# TeknoAmiga.net
KiCad netlist of a schematic drawn in EAGLE
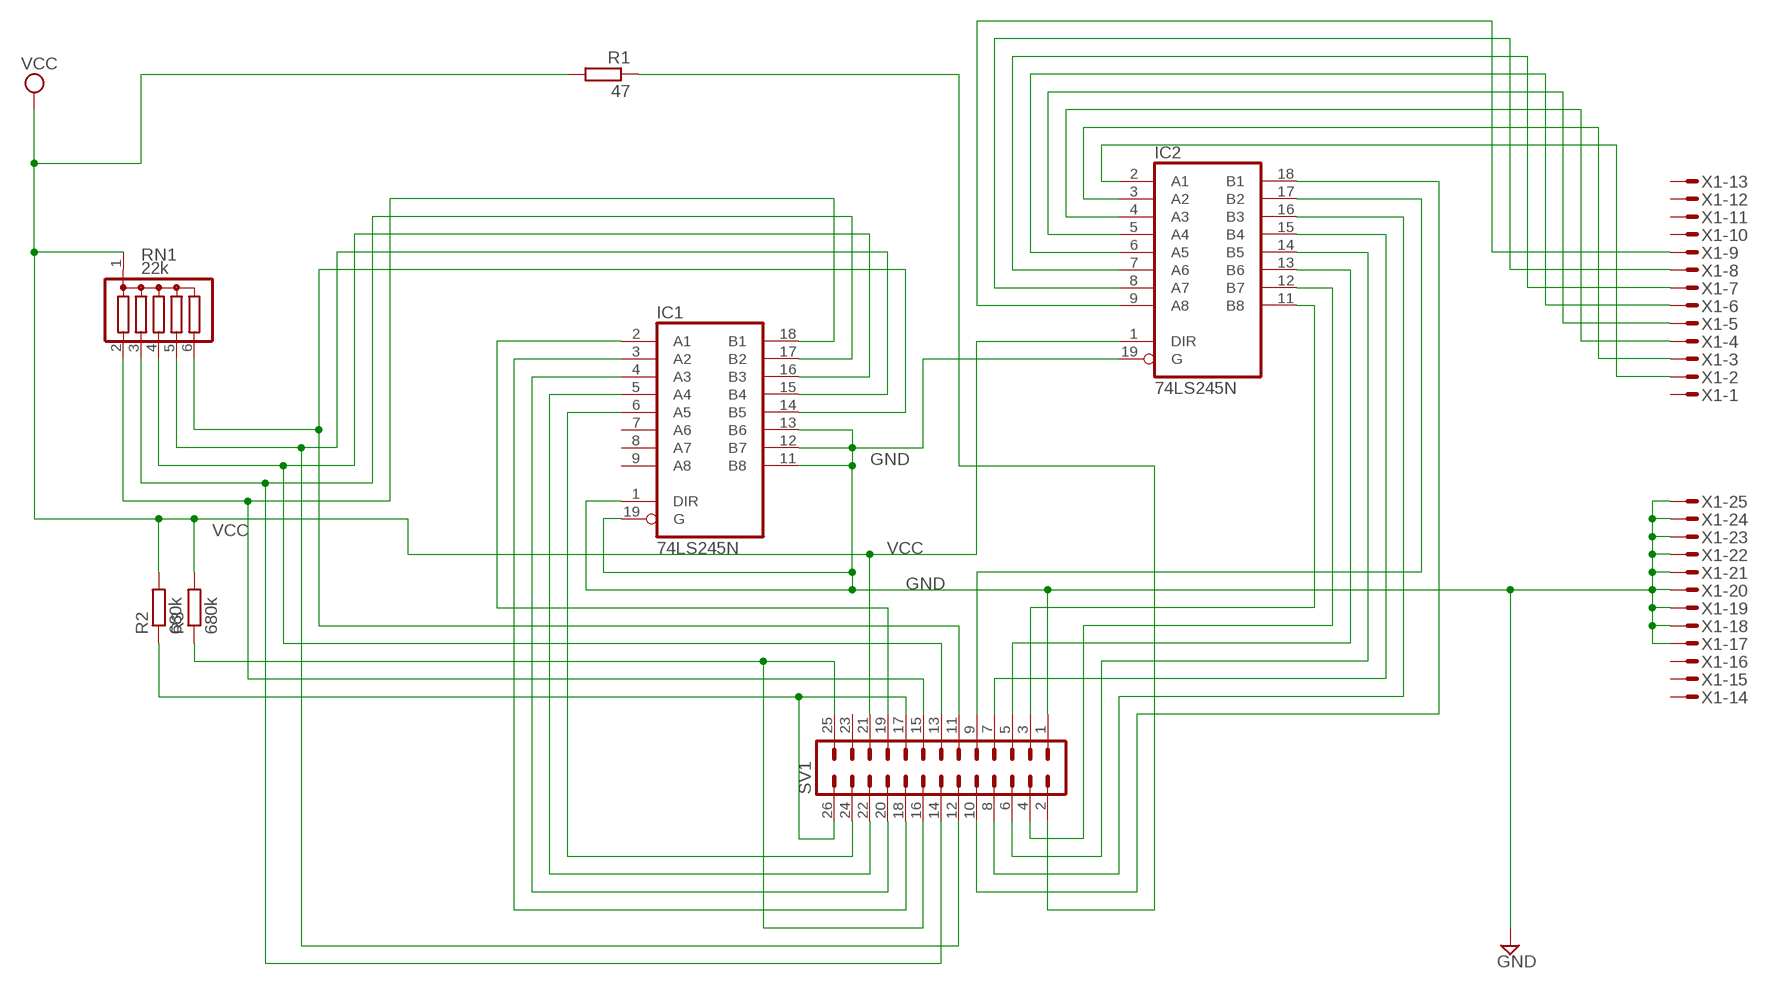
[diagram p0: schematic, sheet 1]

(export (version "E")
  (design (tool "Eeschema 10.0.6"))
  (components
    (comp (ref "IC1")
      (value "74LS245N")
      (footprint "eagle-import:DIL20")
      (libsource (lib "eagle-import") (part "74245NLS"))
    )
    (comp (ref "IC2")
      (value "74LS245N")
      (footprint "eagle-import:DIL20")
      (libsource (lib "eagle-import") (part "74245NLS"))
    )
    (comp (ref "R1")
      (value "47")
      (footprint "eagle-import:0207_12")
      (libsource (lib "eagle-import") (part "R-EU_0207/12"))
    )
    (comp (ref "R2")
      (value "680k")
      (footprint "eagle-import:0207_12")
      (libsource (lib "eagle-import") (part "R-EU_0207/12"))
    )
    (comp (ref "R3")
      (value "680k")
      (footprint "eagle-import:0207_12")
      (libsource (lib "eagle-import") (part "R-EU_0207/12"))
    )
    (comp (ref "RN1")
      (value "22k")
      (footprint "eagle-import:SIL6")
      (libsource (lib "eagle-import") (part "G05R"))
    )
    (comp (ref "SV1")
      (value "MA13-2")
      (footprint "eagle-import:MA13-2")
      (libsource (lib "eagle-import") (part "MA13-2"))
    )
    (comp (ref "X1")
      (value "M25HPS")
      (footprint "eagle-import:M25HP")
      (libsource (lib "eagle-import") (part "M25?SHP"))
    )
  )
  (nets
    (net (code "1") (name "GND") (class "Default")
      (node (ref "IC1") (pin "1") (pinfunction "DIR_1") (pintype "input"))
      (node (ref "IC1") (pin "11") (pinfunction "B8_11") (pintype "bidirectional"))
      (node (ref "IC1") (pin "12") (pinfunction "B7_12") (pintype "bidirectional"))
      (node (ref "IC1") (pin "13") (pinfunction "B6_13") (pintype "bidirectional"))
      (node (ref "IC1") (pin "19") (pinfunction "G_19") (pintype "input"))
      (node (ref "IC2") (pin "19") (pinfunction "G_19") (pintype "input"))
      (node (ref "SV1") (pin "1") (pinfunction "1_1") (pintype "passive"))
      (node (ref "X1") (pin "17") (pinfunction "M_17") (pintype "passive"))
      (node (ref "X1") (pin "18") (pinfunction "M_18") (pintype "passive"))
      (node (ref "X1") (pin "19") (pinfunction "M_19") (pintype "passive"))
      (node (ref "X1") (pin "20") (pinfunction "M_20") (pintype "passive"))
      (node (ref "X1") (pin "21") (pinfunction "M_21") (pintype "passive"))
      (node (ref "X1") (pin "22") (pinfunction "M_22") (pintype "passive"))
      (node (ref "X1") (pin "23") (pinfunction "M_23") (pintype "passive"))
      (node (ref "X1") (pin "24") (pinfunction "M_24") (pintype "passive"))
      (node (ref "X1") (pin "25") (pinfunction "M_25") (pintype "passive"))
    )
    (net (code "2") (name "Net-(IC1A-A1)") (class "Default")
      (node (ref "IC1") (pin "2") (pinfunction "A1_2") (pintype "bidirectional"))
      (node (ref "SV1") (pin "19") (pinfunction "19_19") (pintype "passive"))
    )
    (net (code "3") (name "Net-(IC1A-A2)") (class "Default")
      (node (ref "IC1") (pin "3") (pinfunction "A2_3") (pintype "bidirectional"))
      (node (ref "SV1") (pin "18") (pinfunction "18_18") (pintype "passive"))
    )
    (net (code "4") (name "Net-(IC1A-A3)") (class "Default")
      (node (ref "IC1") (pin "4") (pinfunction "A3_4") (pintype "bidirectional"))
      (node (ref "SV1") (pin "20") (pinfunction "20_20") (pintype "passive"))
    )
    (net (code "5") (name "Net-(IC1A-A4)") (class "Default")
      (node (ref "IC1") (pin "5") (pinfunction "A4_5") (pintype "bidirectional"))
      (node (ref "SV1") (pin "22") (pinfunction "22_22") (pintype "passive"))
    )
    (net (code "6") (name "Net-(IC1A-A5)") (class "Default")
      (node (ref "IC1") (pin "6") (pinfunction "A5_6") (pintype "bidirectional"))
      (node (ref "SV1") (pin "24") (pinfunction "24_24") (pintype "passive"))
    )
    (net (code "7") (name "Net-(IC1A-B1)") (class "Default")
      (node (ref "IC1") (pin "18") (pinfunction "B1_18") (pintype "bidirectional"))
      (node (ref "RN1") (pin "2") (pinfunction "2_2") (pintype "passive"))
      (node (ref "SV1") (pin "15") (pinfunction "15_15") (pintype "passive"))
    )
    (net (code "8") (name "Net-(IC1A-B2)") (class "Default")
      (node (ref "IC1") (pin "17") (pinfunction "B2_17") (pintype "bidirectional"))
      (node (ref "RN1") (pin "3") (pinfunction "3_3") (pintype "passive"))
      (node (ref "SV1") (pin "14") (pinfunction "14_14") (pintype "passive"))
    )
    (net (code "9") (name "Net-(IC1A-B3)") (class "Default")
      (node (ref "IC1") (pin "16") (pinfunction "B3_16") (pintype "bidirectional"))
      (node (ref "RN1") (pin "4") (pinfunction "4_4") (pintype "passive"))
      (node (ref "SV1") (pin "13") (pinfunction "13_13") (pintype "passive"))
    )
    (net (code "10") (name "Net-(IC1A-B4)") (class "Default")
      (node (ref "IC1") (pin "15") (pinfunction "B4_15") (pintype "bidirectional"))
      (node (ref "RN1") (pin "5") (pinfunction "5_5") (pintype "passive"))
      (node (ref "SV1") (pin "12") (pinfunction "12_12") (pintype "passive"))
    )
    (net (code "11") (name "Net-(IC1A-B5)") (class "Default")
      (node (ref "IC1") (pin "14") (pinfunction "B5_14") (pintype "bidirectional"))
      (node (ref "RN1") (pin "6") (pinfunction "6_6") (pintype "passive"))
      (node (ref "SV1") (pin "11") (pinfunction "11_11") (pintype "passive"))
    )
    (net (code "12") (name "Net-(IC2A-A1)") (class "Default")
      (node (ref "IC2") (pin "2") (pinfunction "A1_2") (pintype "bidirectional"))
      (node (ref "X1") (pin "2") (pinfunction "M_2") (pintype "passive"))
    )
    (net (code "13") (name "Net-(IC2A-A2)") (class "Default")
      (node (ref "IC2") (pin "3") (pinfunction "A2_3") (pintype "bidirectional"))
      (node (ref "X1") (pin "3") (pinfunction "M_3") (pintype "passive"))
    )
    (net (code "14") (name "Net-(IC2A-A3)") (class "Default")
      (node (ref "IC2") (pin "4") (pinfunction "A3_4") (pintype "bidirectional"))
      (node (ref "X1") (pin "4") (pinfunction "M_4") (pintype "passive"))
    )
    (net (code "15") (name "Net-(IC2A-A4)") (class "Default")
      (node (ref "IC2") (pin "5") (pinfunction "A4_5") (pintype "bidirectional"))
      (node (ref "X1") (pin "5") (pinfunction "M_5") (pintype "passive"))
    )
    (net (code "16") (name "Net-(IC2A-A5)") (class "Default")
      (node (ref "IC2") (pin "6") (pinfunction "A5_6") (pintype "bidirectional"))
      (node (ref "X1") (pin "6") (pinfunction "M_6") (pintype "passive"))
    )
    (net (code "17") (name "Net-(IC2A-A6)") (class "Default")
      (node (ref "IC2") (pin "7") (pinfunction "A6_7") (pintype "bidirectional"))
      (node (ref "X1") (pin "7") (pinfunction "M_7") (pintype "passive"))
    )
    (net (code "18") (name "Net-(IC2A-A7)") (class "Default")
      (node (ref "IC2") (pin "8") (pinfunction "A7_8") (pintype "bidirectional"))
      (node (ref "X1") (pin "8") (pinfunction "M_8") (pintype "passive"))
    )
    (net (code "19") (name "Net-(IC2A-A8)") (class "Default")
      (node (ref "IC2") (pin "9") (pinfunction "A8_9") (pintype "bidirectional"))
      (node (ref "X1") (pin "9") (pinfunction "M_9") (pintype "passive"))
    )
    (net (code "20") (name "Net-(IC2A-B1)") (class "Default")
      (node (ref "IC2") (pin "18") (pinfunction "B1_18") (pintype "bidirectional"))
      (node (ref "SV1") (pin "10") (pinfunction "10_10") (pintype "passive"))
    )
    (net (code "21") (name "Net-(IC2A-B2)") (class "Default")
      (node (ref "IC2") (pin "17") (pinfunction "B2_17") (pintype "bidirectional"))
      (node (ref "SV1") (pin "9") (pinfunction "9_9") (pintype "passive"))
    )
    (net (code "22") (name "Net-(IC2A-B3)") (class "Default")
      (node (ref "IC2") (pin "16") (pinfunction "B3_16") (pintype "bidirectional"))
      (node (ref "SV1") (pin "8") (pinfunction "8_8") (pintype "passive"))
    )
    (net (code "23") (name "Net-(IC2A-B4)") (class "Default")
      (node (ref "IC2") (pin "15") (pinfunction "B4_15") (pintype "bidirectional"))
      (node (ref "SV1") (pin "7") (pinfunction "7_7") (pintype "passive"))
    )
    (net (code "24") (name "Net-(IC2A-B5)") (class "Default")
      (node (ref "IC2") (pin "14") (pinfunction "B5_14") (pintype "bidirectional"))
      (node (ref "SV1") (pin "6") (pinfunction "6_6") (pintype "passive"))
    )
    (net (code "25") (name "Net-(IC2A-B6)") (class "Default")
      (node (ref "IC2") (pin "13") (pinfunction "B6_13") (pintype "bidirectional"))
      (node (ref "SV1") (pin "5") (pinfunction "5_5") (pintype "passive"))
    )
    (net (code "26") (name "Net-(IC2A-B7)") (class "Default")
      (node (ref "IC2") (pin "12") (pinfunction "B7_12") (pintype "bidirectional"))
      (node (ref "SV1") (pin "4") (pinfunction "4_4") (pintype "passive"))
    )
    (net (code "27") (name "Net-(IC2A-B8)") (class "Default")
      (node (ref "IC2") (pin "11") (pinfunction "B8_11") (pintype "bidirectional"))
      (node (ref "SV1") (pin "3") (pinfunction "3_3") (pintype "passive"))
    )
    (net (code "28") (name "Net-(R1-Pad1)") (class "Default")
      (node (ref "R1") (pin "1") (pinfunction "1_1") (pintype "passive"))
      (node (ref "SV1") (pin "2") (pinfunction "2_2") (pintype "passive"))
    )
    (net (code "29") (name "Net-(R2-Pad1)") (class "Default")
      (node (ref "R2") (pin "1") (pinfunction "1_1") (pintype "passive"))
      (node (ref "SV1") (pin "17") (pinfunction "17_17") (pintype "passive"))
      (node (ref "SV1") (pin "26") (pinfunction "26_26") (pintype "passive"))
    )
    (net (code "30") (name "Net-(R3-Pad1)") (class "Default")
      (node (ref "R3") (pin "1") (pinfunction "1_1") (pintype "passive"))
      (node (ref "SV1") (pin "16") (pinfunction "16_16") (pintype "passive"))
      (node (ref "SV1") (pin "25") (pinfunction "25_25") (pintype "passive"))
    )
    (net (code "31") (name "VCC") (class "Default")
      (node (ref "IC2") (pin "1") (pinfunction "DIR_1") (pintype "input"))
      (node (ref "R1") (pin "2") (pinfunction "2_2") (pintype "passive"))
      (node (ref "R2") (pin "2") (pinfunction "2_2") (pintype "passive"))
      (node (ref "R3") (pin "2") (pinfunction "2_2") (pintype "passive"))
      (node (ref "RN1") (pin "1") (pinfunction "1_1") (pintype "passive"))
      (node (ref "SV1") (pin "21") (pinfunction "21_21") (pintype "passive"))
    )
    (net (code "32") (name "unconnected-(IC1A-A6-Pad7)") (class "Default")
      (node (ref "IC1") (pin "7") (pinfunction "A6_7") (pintype "bidirectional"))
    )
    (net (code "33") (name "unconnected-(IC1A-A7-Pad8)") (class "Default")
      (node (ref "IC1") (pin "8") (pinfunction "A7_8") (pintype "bidirectional"))
    )
    (net (code "34") (name "unconnected-(IC1A-A8-Pad9)") (class "Default")
      (node (ref "IC1") (pin "9") (pinfunction "A8_9") (pintype "bidirectional"))
    )
    (net (code "35") (name "unconnected-(SV1-Pad23)") (class "Default")
      (node (ref "SV1") (pin "23") (pinfunction "23_23") (pintype "passive"))
    )
    (net (code "36") (name "unconnected-(X1A-M-Pad1)") (class "Default")
      (node (ref "X1") (pin "1") (pinfunction "M_1") (pintype "passive"))
    )
    (net (code "37") (name "unconnected-(X1B-M-Pad10)") (class "Default")
      (node (ref "X1") (pin "10") (pinfunction "M_10") (pintype "passive"))
    )
    (net (code "38") (name "unconnected-(X1C-M-Pad11)") (class "Default")
      (node (ref "X1") (pin "11") (pinfunction "M_11") (pintype "passive"))
    )
    (net (code "39") (name "unconnected-(X1D-M-Pad12)") (class "Default")
      (node (ref "X1") (pin "12") (pinfunction "M_12") (pintype "passive"))
    )
    (net (code "40") (name "unconnected-(X1E-M-Pad13)") (class "Default")
      (node (ref "X1") (pin "13") (pinfunction "M_13") (pintype "passive"))
    )
    (net (code "41") (name "unconnected-(X1F-M-Pad14)") (class "Default")
      (node (ref "X1") (pin "14") (pinfunction "M_14") (pintype "passive"))
    )
    (net (code "42") (name "unconnected-(X1G-M-Pad15)") (class "Default")
      (node (ref "X1") (pin "15") (pinfunction "M_15") (pintype "passive"))
    )
    (net (code "43") (name "unconnected-(X1H-M-Pad16)") (class "Default")
      (node (ref "X1") (pin "16") (pinfunction "M_16") (pintype "passive"))
    )
  )
)
